# Altimiter_SCH.net
KiCad netlist of a schematic drawn in Altium Designer
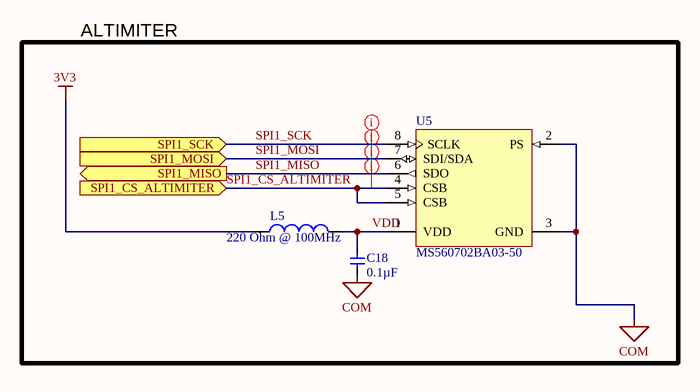
[diagram p0: Altimiter_SCH.SchDoc]

(export (version "E")
  (design (tool "Eeschema 10.0.6"))
  (components
    (comp (ref "C18")
      (value "GRM188R71C104KA01D")
      (footprint "C0603")
      (description "CAP CER 0.1UF 16V 10% X7R 0603")
      (fields (field (name "TOLERANCE") "±10%") (field (name "CAPACITANCE") "0.1µF"))
      (libsource (lib "Rockets_2015-2016") (part "GRM188R71C104KA01D"))
    )
    (comp (ref "L5")
      (value "BLM21PG221SN1D")
      (footprint "L0805")
      (description "FERRITE CHIP 220 OHM 0805")
      (fields (field (name "IMPEDANCE @ FREQUENCY") "220 Ohm @ 100MHz"))
      (libsource (lib "Rockets_2015-2016") (part "BLM21PG221SN1D"))
    )
    (comp (ref "U5")
      (value "MS560702BA03-50")
      (footprint "TECO-MS560702BA03-50_V")
      (fields (field (name "MANUFACTURER") "TE Connectivity"))
      (libsource (lib "Altium Content Vault") (part "TECO-MS560702BA03-8"))
    )
  )
  (nets
    (net (code "1") (name "/SPI1_CS_ALTIMITER") (class "Default")
      (node (ref "U5") (pin "4") (pinfunction "CSB_4") (pintype "input"))
      (node (ref "U5") (pin "5") (pinfunction "CSB_5") (pintype "input"))
    )
    (net (code "2") (name "/SPI1_MISO") (class "Default")
      (node (ref "U5") (pin "6") (pinfunction "SDO_6") (pintype "output"))
    )
    (net (code "3") (name "/SPI1_MOSI") (class "Default")
      (node (ref "U5") (pin "7") (pinfunction "SDI/SDA_7") (pintype "bidirectional"))
    )
    (net (code "4") (name "/SPI1_SCK") (class "Default")
      (node (ref "U5") (pin "8") (pinfunction "SCLK_8") (pintype "input"))
    )
    (net (code "5") (name "/VDD") (class "Default")
      (node (ref "C18") (pin "1") (pinfunction "1_1") (pintype "passive"))
      (node (ref "L5") (pin "2") (pinfunction "2_2") (pintype "passive"))
      (node (ref "U5") (pin "1") (pinfunction "VDD_1") (pintype "power_in"))
    )
    (net (code "6") (name "3V3") (class "Default")
      (node (ref "L5") (pin "1") (pinfunction "1_1") (pintype "passive"))
    )
    (net (code "7") (name "COM") (class "Default")
      (node (ref "C18") (pin "2") (pinfunction "2_2") (pintype "passive"))
      (node (ref "U5") (pin "2") (pinfunction "PS_2") (pintype "input"))
      (node (ref "U5") (pin "3") (pinfunction "GND_3") (pintype "power_in"))
    )
  )
)
